# Sum-Comp.net
KiCad netlist of a schematic drawn in Altium Designer
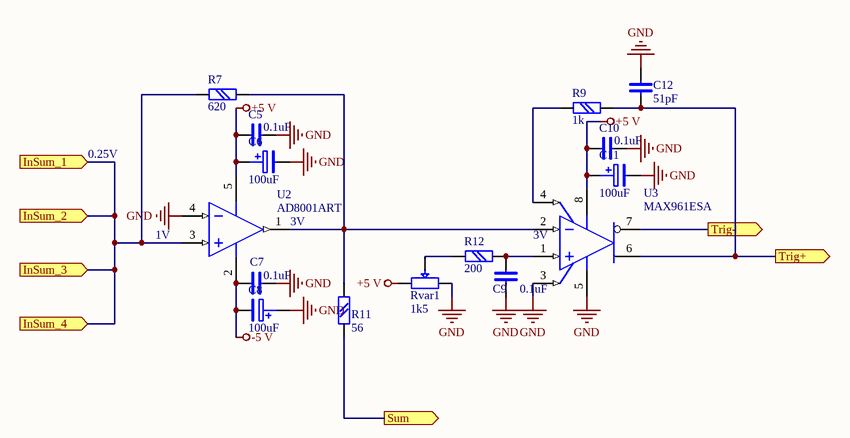
[diagram p0: Sum-Comp.SchDoc]

(export (version "E")
  (design (tool "Eeschema 10.0.6"))
  (components
    (comp (ref "C5") (value "0.1uF") (footprint "chip0805") (libsource (lib "vDevice") (part "C")))
    (comp (ref "C6") (value "100uF") (footprint "CEL-SMD300") (libsource (lib "vDevice") (part "C POL")))
    (comp (ref "C7") (value "0.1uF") (footprint "chip0805") (libsource (lib "vDevice") (part "C")))
    (comp (ref "C8") (value "100uF") (footprint "CEL-SMD300") (libsource (lib "vDevice") (part "C POL")))
    (comp (ref "C9") (value "0.1uF") (footprint "chip0805") (libsource (lib "vDevice") (part "C")))
    (comp (ref "C10") (value "0.1uF") (footprint "chip0805") (libsource (lib "vDevice") (part "C")))
    (comp (ref "C11") (value "100uF") (footprint "CEL-SMD300") (libsource (lib "vDevice") (part "C POL")))
    (comp (ref "C12") (value "51pF") (footprint "chip0805") (libsource (lib "vDevice") (part "C")))
    (comp (ref "R7") (value "620") (footprint "chip0805") (libsource (lib "vDevice") (part "R")))
    (comp (ref "R9") (value "1k") (footprint "chip0805") (libsource (lib "vDevice") (part "R")))
    (comp (ref "R11") (value "56") (footprint "chip0805") (libsource (lib "vDevice") (part "R")))
    (comp (ref "R12") (value "200") (footprint "chip0805") (libsource (lib "vDevice") (part "R")))
    (comp (ref "Rvar1") (value "1k5") (footprint "RVAR1") (libsource (lib "vDevice") (part "R VAR")))
    (comp (ref "U2")
      (value "AD8001ART")
      (footprint "RT-5")
      (description "Low Cost, 300MHz Voltage Feedback Amplifier")
      (fields (field (name "PUBLISHER") "Altium Limited"))
      (libsource (lib "AD Operational Amplifier") (part "AD8055ART"))
    )
    (comp (ref "U3")
      (value "MAX961ESA")
      (footprint "NSO8_N")
      (description "Single Ultra-High-Speed, +3V/+5V, Beyond-the-Rails Comparator")
      (fields (field (name "PUBLISHER") "Altium Limited"))
      (libsource (lib "Maxim Analog Comparator") (part "MAX961ESA"))
    )
  )
  (nets
    (net (code "1") (name "+5 V") (class "Default")
      (node (ref "C10") (pin "2") (pinfunction "2_2") (pintype "passive"))
      (node (ref "C11") (pin "+") (pinfunction "+_+") (pintype "passive"))
      (node (ref "C5") (pin "2") (pinfunction "2_2") (pintype "passive"))
      (node (ref "C6") (pin "+") (pinfunction "+_+") (pintype "passive"))
      (node (ref "Rvar1") (pin "1") (pinfunction "1_1") (pintype "passive"))
      (node (ref "U2") (pin "5") (pinfunction "V+_5") (pintype "power_in"))
      (node (ref "U3") (pin "8") (pinfunction "V+_8") (pintype "power_in"))
    )
    (net (code "2") (name "-5 V") (class "Default")
      (node (ref "C7") (pin "2") (pinfunction "2_2") (pintype "passive"))
      (node (ref "C8") (pin "-") (pinfunction "-_-") (pintype "passive"))
      (node (ref "U2") (pin "2") (pinfunction "V-_2") (pintype "power_in"))
    )
    (net (code "3") (name "/InSum_1") (class "Default")
      (node (ref "R7") (pin "1") (pinfunction "1_1") (pintype "passive"))
      (node (ref "U2") (pin "3") (pinfunction "IN+_3") (pintype "input"))
    )
    (net (code "4") (name "/Sum") (class "Default")
      (node (ref "R11") (pin "1") (pinfunction "1_1") (pintype "passive"))
    )
    (net (code "5") (name "/Trig+") (class "Default")
      (node (ref "C12") (pin "2") (pinfunction "2_2") (pintype "passive"))
      (node (ref "R9") (pin "2") (pinfunction "2_2") (pintype "passive"))
      (node (ref "U3") (pin "6") (pinfunction "Q_6") (pintype "tri_state"))
    )
    (net (code "6") (name "/Trig-") (class "Default")
      (node (ref "U3") (pin "7") (pinfunction "~{Q}_7") (pintype "tri_state"))
    )
    (net (code "7") (name "GND") (class "Default")
      (node (ref "C10") (pin "1") (pinfunction "1_1") (pintype "passive"))
      (node (ref "C11") (pin "-") (pinfunction "-_-") (pintype "passive"))
      (node (ref "C12") (pin "1") (pinfunction "1_1") (pintype "passive"))
      (node (ref "C5") (pin "1") (pinfunction "1_1") (pintype "passive"))
      (node (ref "C6") (pin "-") (pinfunction "-_-") (pintype "passive"))
      (node (ref "C7") (pin "1") (pinfunction "1_1") (pintype "passive"))
      (node (ref "C8") (pin "+") (pinfunction "+_+") (pintype "passive"))
      (node (ref "C9") (pin "1") (pinfunction "1_1") (pintype "passive"))
      (node (ref "Rvar1") (pin "3") (pinfunction "3_3") (pintype "passive"))
      (node (ref "U2") (pin "4") (pinfunction "IN-_4") (pintype "input"))
      (node (ref "U3") (pin "3") (pinfunction "SHDN_3") (pintype "input"))
      (node (ref "U3") (pin "5") (pinfunction "GND_5") (pintype "power_in"))
    )
    (net (code "8") (name "Net-(R12-Pad1)") (class "Default")
      (node (ref "R12") (pin "1") (pinfunction "1_1") (pintype "passive"))
      (node (ref "Rvar1") (pin "2") (pinfunction "2_2") (pintype "passive"))
    )
    (net (code "9") (name "Net-(U2-OUT)") (class "Default")
      (node (ref "R11") (pin "2") (pinfunction "2_2") (pintype "passive"))
      (node (ref "R7") (pin "2") (pinfunction "2_2") (pintype "passive"))
      (node (ref "U2") (pin "1") (pinfunction "OUT_1") (pintype "output"))
      (node (ref "U3") (pin "2") (pinfunction "IN-_2") (pintype "input"))
    )
    (net (code "10") (name "Net-(U3-IN+)") (class "Default")
      (node (ref "C9") (pin "2") (pinfunction "2_2") (pintype "passive"))
      (node (ref "R12") (pin "2") (pinfunction "2_2") (pintype "passive"))
      (node (ref "U3") (pin "1") (pinfunction "IN+_1") (pintype "input"))
    )
    (net (code "11") (name "Net-(U3-LE)") (class "Default")
      (node (ref "R9") (pin "1") (pinfunction "1_1") (pintype "passive"))
      (node (ref "U3") (pin "4") (pinfunction "LE_4") (pintype "input"))
    )
  )
)
